# Power_Main_Regulators.net
KiCad netlist of a schematic drawn in Altium Designer
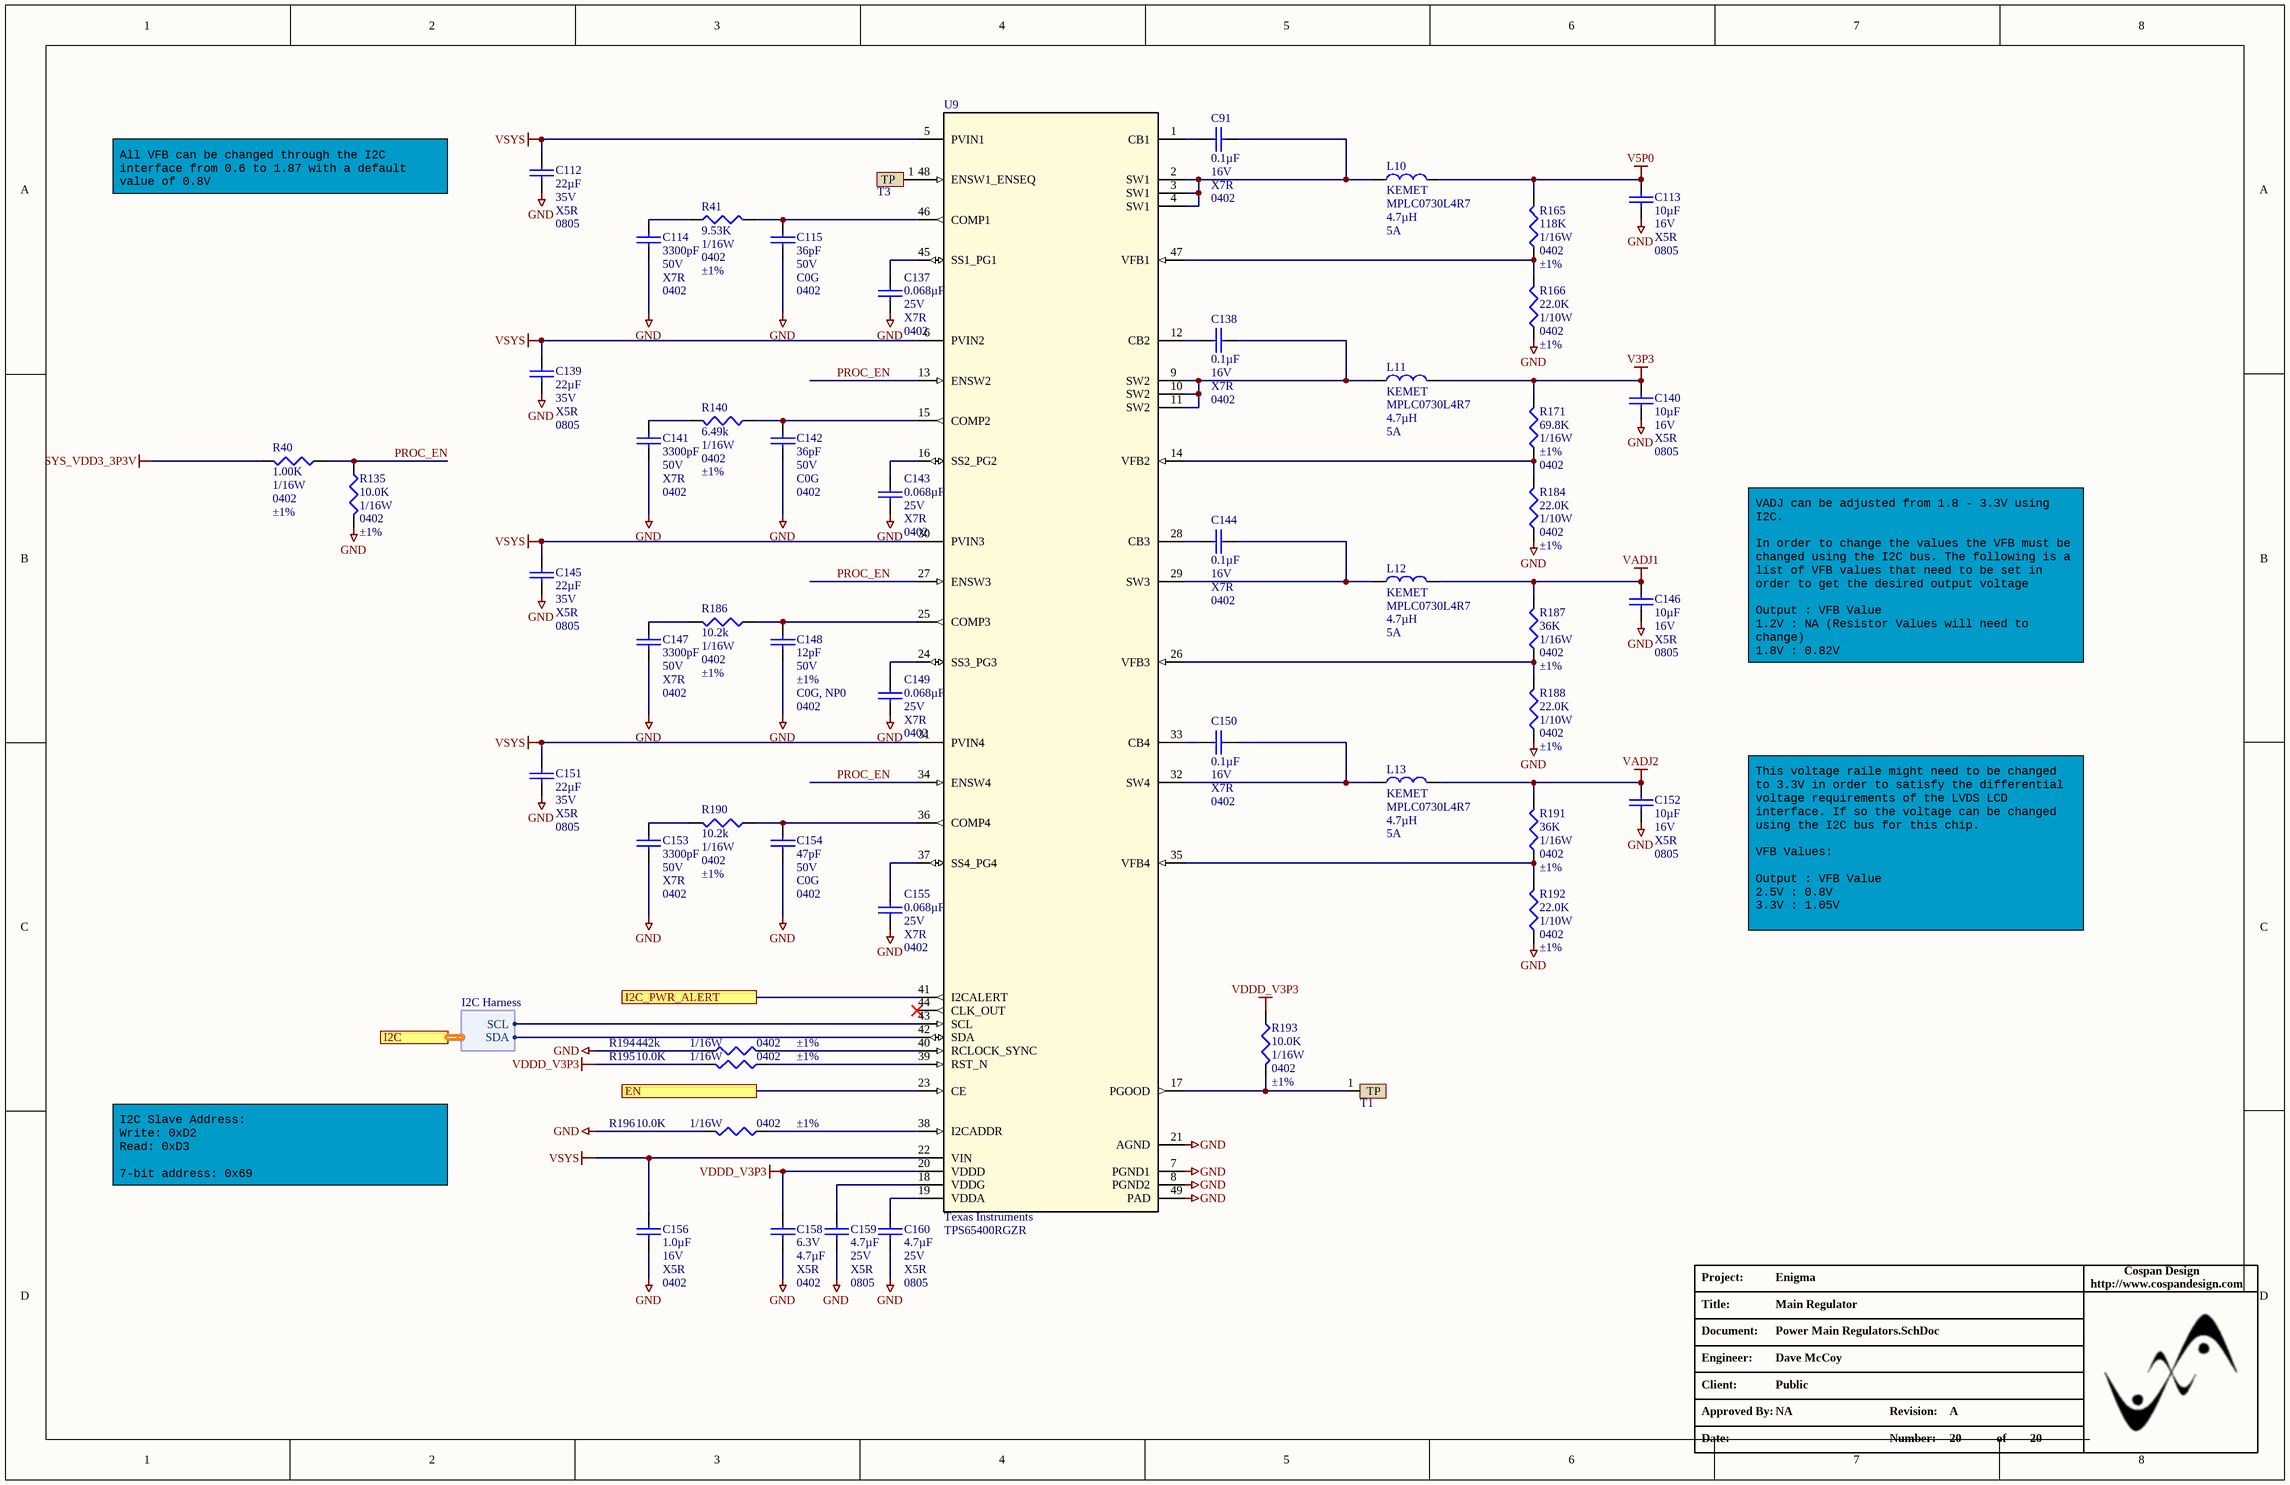
[diagram p0: Power Main Regulators.SchDoc]

(export (version "E")
  (design (tool "Eeschema 10.0.6"))
  (components
    (comp (ref "C91")
      (value "0.1uF")
      (footprint "C_0402")
      (description "CAP CER .10UF 16V X7R 0402")
      (fields
        (field (name "MANUFACTURER") "Murata Electronics North America")
        (field (name "MANUFACTURER PART NUMBER") "GRM155R71C104KA88J")
        (field (name "CAPACITANCE") "0.1µF")
        (field (name "VOLTAGE - RATED") "16V")
        (field (name "TEMPERATURE COEFFICIENT") "X7R")
        (field (name "PACKAGE / CASE") "0402")
      )
      (libsource (lib "Main LibraryX") (part "C_0402_0.1UF_16V"))
    )
    (comp (ref "C112")
      (value "C_0805_22µF_35V")
      (footprint "C_ERA-0805")
      (description "CAP CER 22UF 35V X5R 0805")
      (fields
        (field (name "MANUFACTURER") "TDK Corporation")
        (field (name "MANUFACTURER PART NUMBER") "C2012X5R1V226M125AC")
        (field (name "CAPACITANCE") "22µF")
        (field (name "VOLTAGE - RATED") "35V")
        (field (name "TEMPERATURE COEFFICIENT") "X5R")
        (field (name "PACKAGE / CASE") "0805")
      )
      (libsource (lib "Cospan Design") (part "C_0805_22µF_35V"))
    )
    (comp (ref "C113")
      (value "10µF")
      (footprint "C_ERA-0805")
      (description "CAP CER 10uF 16V X5R 20% 0805")
      (fields
        (field (name "MANUFACTURER") "Taiyo Yuden")
        (field (name "MANUFACTURER PART NUMBER") "EMK212BJ106KG-T")
        (field (name "CAPACITANCE") "10µF")
        (field (name "VOLTAGE - RATED") "16V")
        (field (name "TEMPERATURE COEFFICIENT") "X5R")
        (field (name "PACKAGE / CASE") "0805")
      )
      (libsource (lib "Main LibraryX") (part "C_0805_10UF_16V"))
    )
    (comp (ref "C114")
      (value "C_0402_3.3nF_50V")
      (footprint "C_0402")
      (fields
        (field (name "MANUFACTURER") "Murata Electronics North America")
        (field (name "MANUFACTURER PART NUMBER") "GRM155R71H332KA01D")
        (field (name "TOLERANCE") "±10%")
        (field (name "CAPACITANCE") "3300pF")
        (field (name "VOLTAGE - RATED") "50V")
        (field (name "TEMPERATURE COEFFICIENT") "X7R")
        (field (name "PACKAGE / CASE") "0402")
      )
      (libsource (lib "Main LibraryX") (part "C_0402_3.3nF_50V"))
    )
    (comp (ref "C115")
      (value "C_0402_36pF")
      (footprint "C_0402")
      (description "CAP CER 36PF 50V NP0 0402")
      (fields
        (field (name "MANUFACTURER") "Samsung Electro-Mechanics America, Inc.")
        (field (name "MANUFACTURER PART NUMBER") "CL05C360JB5NNNC")
        (field (name "CAPACITANCE") "36pF")
        (field (name "VOLTAGE - RATED") "50V")
        (field (name "TEMPERATURE COEFFICIENT") "C0G")
        (field (name "PACKAGE / CASE") "0402")
      )
      (libsource (lib "Cospan Design") (part "C_0402_36pF"))
    )
    (comp (ref "C137")
      (value "C_0402_68nF")
      (footprint "C_0402")
      (description "CAP CER 0.068UF 25V X7R 0402")
      (fields
        (field (name "MANUFACTURER") "Murata Electronics North America")
        (field (name "MANUFACTURER PART NUMBER") "GRM155R71E683KE14D")
        (field (name "CAPACITANCE") "0.068µF")
        (field (name "VOLTAGE - RATED") "25V")
        (field (name "TEMPERATURE COEFFICIENT") "X7R")
        (field (name "PACKAGE / CASE") "0402")
      )
      (libsource (lib "Cospan Design") (part "C_0402_68nF"))
    )
    (comp (ref "C138")
      (value "0.1uF")
      (footprint "C_0402")
      (description "CAP CER .10UF 16V X7R 0402")
      (fields
        (field (name "MANUFACTURER") "Murata Electronics North America")
        (field (name "MANUFACTURER PART NUMBER") "GRM155R71C104KA88J")
        (field (name "CAPACITANCE") "0.1µF")
        (field (name "VOLTAGE - RATED") "16V")
        (field (name "TEMPERATURE COEFFICIENT") "X7R")
        (field (name "PACKAGE / CASE") "0402")
      )
      (libsource (lib "Main LibraryX") (part "C_0402_0.1UF_16V"))
    )
    (comp (ref "C139")
      (value "C_0805_22µF_35V")
      (footprint "C_ERA-0805")
      (description "CAP CER 22UF 35V X5R 0805")
      (fields
        (field (name "MANUFACTURER") "TDK Corporation")
        (field (name "MANUFACTURER PART NUMBER") "C2012X5R1V226M125AC")
        (field (name "CAPACITANCE") "22µF")
        (field (name "VOLTAGE - RATED") "35V")
        (field (name "TEMPERATURE COEFFICIENT") "X5R")
        (field (name "PACKAGE / CASE") "0805")
      )
      (libsource (lib "Cospan Design") (part "C_0805_22µF_35V"))
    )
    (comp (ref "C140")
      (value "10µF")
      (footprint "C_ERA-0805")
      (description "CAP CER 10uF 16V X5R 20% 0805")
      (fields
        (field (name "MANUFACTURER") "Taiyo Yuden")
        (field (name "MANUFACTURER PART NUMBER") "EMK212BJ106KG-T")
        (field (name "CAPACITANCE") "10µF")
        (field (name "VOLTAGE - RATED") "16V")
        (field (name "TEMPERATURE COEFFICIENT") "X5R")
        (field (name "PACKAGE / CASE") "0805")
      )
      (libsource (lib "Main LibraryX") (part "C_0805_10UF_16V"))
    )
    (comp (ref "C141")
      (value "C_0402_3.3nF_50V")
      (footprint "C_0402")
      (fields
        (field (name "MANUFACTURER") "Murata Electronics North America")
        (field (name "MANUFACTURER PART NUMBER") "GRM155R71H332KA01D")
        (field (name "TOLERANCE") "±10%")
        (field (name "CAPACITANCE") "3300pF")
        (field (name "VOLTAGE - RATED") "50V")
        (field (name "TEMPERATURE COEFFICIENT") "X7R")
        (field (name "PACKAGE / CASE") "0402")
      )
      (libsource (lib "Main LibraryX") (part "C_0402_3.3nF_50V"))
    )
    (comp (ref "C142")
      (value "C_0402_36pF")
      (footprint "C_0402")
      (description "CAP CER 36PF 50V NP0 0402")
      (fields
        (field (name "MANUFACTURER") "Samsung Electro-Mechanics America, Inc.")
        (field (name "MANUFACTURER PART NUMBER") "CL05C360JB5NNNC")
        (field (name "CAPACITANCE") "36pF")
        (field (name "VOLTAGE - RATED") "50V")
        (field (name "TEMPERATURE COEFFICIENT") "C0G")
        (field (name "PACKAGE / CASE") "0402")
      )
      (libsource (lib "Cospan Design") (part "C_0402_36pF"))
    )
    (comp (ref "C143")
      (value "C_0402_68nF")
      (footprint "C_0402")
      (description "CAP CER 0.068UF 25V X7R 0402")
      (fields
        (field (name "MANUFACTURER") "Murata Electronics North America")
        (field (name "MANUFACTURER PART NUMBER") "GRM155R71E683KE14D")
        (field (name "CAPACITANCE") "0.068µF")
        (field (name "VOLTAGE - RATED") "25V")
        (field (name "TEMPERATURE COEFFICIENT") "X7R")
        (field (name "PACKAGE / CASE") "0402")
      )
      (libsource (lib "Cospan Design") (part "C_0402_68nF"))
    )
    (comp (ref "C144")
      (value "0.1uF")
      (footprint "C_0402")
      (description "CAP CER .10UF 16V X7R 0402")
      (fields
        (field (name "MANUFACTURER") "Murata Electronics North America")
        (field (name "MANUFACTURER PART NUMBER") "GRM155R71C104KA88J")
        (field (name "CAPACITANCE") "0.1µF")
        (field (name "VOLTAGE - RATED") "16V")
        (field (name "TEMPERATURE COEFFICIENT") "X7R")
        (field (name "PACKAGE / CASE") "0402")
      )
      (libsource (lib "Main LibraryX") (part "C_0402_0.1UF_16V"))
    )
    (comp (ref "C145")
      (value "C_0805_22µF_35V")
      (footprint "C_ERA-0805")
      (description "CAP CER 22UF 35V X5R 0805")
      (fields
        (field (name "MANUFACTURER") "TDK Corporation")
        (field (name "MANUFACTURER PART NUMBER") "C2012X5R1V226M125AC")
        (field (name "CAPACITANCE") "22µF")
        (field (name "VOLTAGE - RATED") "35V")
        (field (name "TEMPERATURE COEFFICIENT") "X5R")
        (field (name "PACKAGE / CASE") "0805")
      )
      (libsource (lib "Cospan Design") (part "C_0805_22µF_35V"))
    )
    (comp (ref "C146")
      (value "10µF")
      (footprint "C_ERA-0805")
      (description "CAP CER 10uF 16V X5R 20% 0805")
      (fields
        (field (name "MANUFACTURER") "Taiyo Yuden")
        (field (name "MANUFACTURER PART NUMBER") "EMK212BJ106KG-T")
        (field (name "CAPACITANCE") "10µF")
        (field (name "VOLTAGE - RATED") "16V")
        (field (name "TEMPERATURE COEFFICIENT") "X5R")
        (field (name "PACKAGE / CASE") "0805")
      )
      (libsource (lib "Main LibraryX") (part "C_0805_10UF_16V"))
    )
    (comp (ref "C147")
      (value "C_0402_3.3nF_50V")
      (footprint "C_0402")
      (fields
        (field (name "MANUFACTURER") "Murata Electronics North America")
        (field (name "MANUFACTURER PART NUMBER") "GRM155R71H332KA01D")
        (field (name "TOLERANCE") "±10%")
        (field (name "CAPACITANCE") "3300pF")
        (field (name "VOLTAGE - RATED") "50V")
        (field (name "TEMPERATURE COEFFICIENT") "X7R")
        (field (name "PACKAGE / CASE") "0402")
      )
      (libsource (lib "Main LibraryX") (part "C_0402_3.3nF_50V"))
    )
    (comp (ref "C148")
      (value "12pF")
      (footprint "C_0402")
      (description "CAP CER 12PF 50V 5% C0G 0402")
      (fields
        (field (name "MANUFACTURER") "Murata Electronics North America")
        (field (name "MANUFACTURER PART NUMBER") "GRM1555C1H120FA01D")
        (field (name "CAPACITANCE") "12pF")
        (field (name "VOLTAGE - RATED") "50V")
        (field (name "TOLERANCE") "±1%")
        (field (name "TEMPERATURE COEFFICIENT") "C0G, NP0")
        (field (name "PACKAGE / CASE") "0402")
      )
      (libsource (lib "Main LibraryX") (part "C_0402_12PF_50V"))
    )
    (comp (ref "C149")
      (value "C_0402_68nF")
      (footprint "C_0402")
      (description "CAP CER 0.068UF 25V X7R 0402")
      (fields
        (field (name "MANUFACTURER") "Murata Electronics North America")
        (field (name "MANUFACTURER PART NUMBER") "GRM155R71E683KE14D")
        (field (name "CAPACITANCE") "0.068µF")
        (field (name "VOLTAGE - RATED") "25V")
        (field (name "TEMPERATURE COEFFICIENT") "X7R")
        (field (name "PACKAGE / CASE") "0402")
      )
      (libsource (lib "Cospan Design") (part "C_0402_68nF"))
    )
    (comp (ref "C150")
      (value "0.1uF")
      (footprint "C_0402")
      (description "CAP CER .10UF 16V X7R 0402")
      (fields
        (field (name "MANUFACTURER") "Murata Electronics North America")
        (field (name "MANUFACTURER PART NUMBER") "GRM155R71C104KA88J")
        (field (name "CAPACITANCE") "0.1µF")
        (field (name "VOLTAGE - RATED") "16V")
        (field (name "TEMPERATURE COEFFICIENT") "X7R")
        (field (name "PACKAGE / CASE") "0402")
      )
      (libsource (lib "Main LibraryX") (part "C_0402_0.1UF_16V"))
    )
    (comp (ref "C151")
      (value "C_0805_22µF_35V")
      (footprint "C_ERA-0805")
      (description "CAP CER 22UF 35V X5R 0805")
      (fields
        (field (name "MANUFACTURER") "TDK Corporation")
        (field (name "MANUFACTURER PART NUMBER") "C2012X5R1V226M125AC")
        (field (name "CAPACITANCE") "22µF")
        (field (name "VOLTAGE - RATED") "35V")
        (field (name "TEMPERATURE COEFFICIENT") "X5R")
        (field (name "PACKAGE / CASE") "0805")
      )
      (libsource (lib "Cospan Design") (part "C_0805_22µF_35V"))
    )
    (comp (ref "C152")
      (value "10µF")
      (footprint "C_ERA-0805")
      (description "CAP CER 10uF 16V X5R 20% 0805")
      (fields
        (field (name "MANUFACTURER") "Taiyo Yuden")
        (field (name "MANUFACTURER PART NUMBER") "EMK212BJ106KG-T")
        (field (name "CAPACITANCE") "10µF")
        (field (name "VOLTAGE - RATED") "16V")
        (field (name "TEMPERATURE COEFFICIENT") "X5R")
        (field (name "PACKAGE / CASE") "0805")
      )
      (libsource (lib "Main LibraryX") (part "C_0805_10UF_16V"))
    )
    (comp (ref "C153")
      (value "C_0402_3.3nF_50V")
      (footprint "C_0402")
      (fields
        (field (name "MANUFACTURER") "Murata Electronics North America")
        (field (name "MANUFACTURER PART NUMBER") "GRM155R71H332KA01D")
        (field (name "TOLERANCE") "±10%")
        (field (name "CAPACITANCE") "3300pF")
        (field (name "VOLTAGE - RATED") "50V")
        (field (name "TEMPERATURE COEFFICIENT") "X7R")
        (field (name "PACKAGE / CASE") "0402")
      )
      (libsource (lib "Main LibraryX") (part "C_0402_3.3nF_50V"))
    )
    (comp (ref "C154")
      (value "47pF")
      (footprint "C_0402")
      (description "CAP CER 47PF 50V 5% C0G 0402")
      (fields
        (field (name "MANUFACTURER") "Murata Electronics North America")
        (field (name "MANUFACTURER PART NUMBER") "GRM1555C1H470JA01D")
        (field (name "CAPACITANCE") "47pF")
        (field (name "VOLTAGE - RATED") "50V")
        (field (name "TEMPERATURE COEFFICIENT") "C0G")
        (field (name "PACKAGE / CASE") "0402")
      )
      (libsource (lib "Main Library") (part "C_0402_47p_50V"))
    )
    (comp (ref "C155")
      (value "C_0402_68nF")
      (footprint "C_0402")
      (description "CAP CER 0.068UF 25V X7R 0402")
      (fields
        (field (name "MANUFACTURER") "Murata Electronics North America")
        (field (name "MANUFACTURER PART NUMBER") "GRM155R71E683KE14D")
        (field (name "CAPACITANCE") "0.068µF")
        (field (name "VOLTAGE - RATED") "25V")
        (field (name "TEMPERATURE COEFFICIENT") "X7R")
        (field (name "PACKAGE / CASE") "0402")
      )
      (libsource (lib "Cospan Design") (part "C_0402_68nF"))
    )
    (comp (ref "C156")
      (value "1.0uF")
      (footprint "C_0402")
      (description "CAP CER 1.0UF 16V X5R 0402")
      (fields
        (field (name "TOLERANCE") "10%")
        (field (name "VOLTAGE") "16V")
        (field (name "CAPACITANCE") "1.0µF")
        (field (name "VOLTAGE - RATED") "16V")
        (field (name "TEMPERATURE COEFFICIENT") "X5R")
        (field (name "PACKAGE / CASE") "0402")
      )
      (libsource (lib "Main Library") (part "C_0402_1.0UF_16V"))
    )
    (comp (ref "C158")
      (value "4.7uF")
      (footprint "C_0402")
      (description "CAP CER 4.7UF 6.3V X5R 0402")
      (fields
        (field (name "MANUFACTURER") "Samsung Electro-Mechanics America, Inc")
        (field (name "MANUFACTURER PART NUMBER") "CL05A475MQ5NRNC")
        (field (name "VOLTAGE - RATED") "6.3V")
        (field (name "CAPACITANCE") "4.7µF")
        (field (name "TEMPERATURE COEFFICIENT") "X5R")
        (field (name "PACKAGE / CASE") "0402")
      )
      (libsource (lib "Main Library") (part "C_0402_4.7UF"))
    )
    (comp (ref "C159")
      (value "4.7µF")
      (footprint "C_ERA-0805")
      (description "CAP CER 4.7UF 25V 10% X5R 0805")
      (fields
        (field (name "MANUFACTURER") "Taiyo Yuden")
        (field (name "MANUFACTURER PART NUMBER") "TMK212BJ475KG-T")
        (field (name "CAPACITANCE") "4.7µF")
        (field (name "VOLTAGE - RATED") "25V")
        (field (name "TEMPERATURE COEFFICIENT") "X5R")
        (field (name "PACKAGE / CASE") "0805")
      )
      (libsource (lib "Main Library") (part "C_0805_4.7µF_25V"))
    )
    (comp (ref "C160")
      (value "4.7µF")
      (footprint "C_ERA-0805")
      (description "CAP CER 4.7UF 25V 10% X5R 0805")
      (fields
        (field (name "MANUFACTURER") "Taiyo Yuden")
        (field (name "MANUFACTURER PART NUMBER") "TMK212BJ475KG-T")
        (field (name "CAPACITANCE") "4.7µF")
        (field (name "VOLTAGE - RATED") "25V")
        (field (name "TEMPERATURE COEFFICIENT") "X5R")
        (field (name "PACKAGE / CASE") "0805")
      )
      (libsource (lib "Main Library") (part "C_0805_4.7µF_25V"))
    )
    (comp (ref "L10")
      (value "L_MPLC0730L4R7")
      (footprint "KEM_L9004_MPLC")
      (description "FIXED IND 4.7UH 5A 41 MOHM SMD")
      (fields
        (field (name "TOLERANCE") "±20%")
        (field (name "MANUFACTURER") "KEMET")
        (field (name "MANUFACTURER PART NUMBER") "MPLC0730L4R7")
        (field (name "INDUCTANCE") "4.7µH")
        (field (name "MAX DC CURRENT") "5A")
      )
      (libsource (lib "Cospan Design") (part "L_MPLC0730L4R7"))
    )
    (comp (ref "L11")
      (value "L_MPLC0730L4R7")
      (footprint "KEM_L9004_MPLC")
      (description "FIXED IND 4.7UH 5A 41 MOHM SMD")
      (fields
        (field (name "TOLERANCE") "±20%")
        (field (name "MANUFACTURER") "KEMET")
        (field (name "MANUFACTURER PART NUMBER") "MPLC0730L4R7")
        (field (name "INDUCTANCE") "4.7µH")
        (field (name "MAX DC CURRENT") "5A")
      )
      (libsource (lib "Cospan Design") (part "L_MPLC0730L4R7"))
    )
    (comp (ref "L12")
      (value "L_MPLC0730L4R7")
      (footprint "KEM_L9004_MPLC")
      (description "FIXED IND 4.7UH 5A 41 MOHM SMD")
      (fields
        (field (name "TOLERANCE") "±20%")
        (field (name "MANUFACTURER") "KEMET")
        (field (name "MANUFACTURER PART NUMBER") "MPLC0730L4R7")
        (field (name "INDUCTANCE") "4.7µH")
        (field (name "MAX DC CURRENT") "5A")
      )
      (libsource (lib "Cospan Design") (part "L_MPLC0730L4R7"))
    )
    (comp (ref "L13")
      (value "L_MPLC0730L4R7")
      (footprint "KEM_L9004_MPLC")
      (description "FIXED IND 4.7UH 5A 41 MOHM SMD")
      (fields
        (field (name "TOLERANCE") "±20%")
        (field (name "MANUFACTURER") "KEMET")
        (field (name "MANUFACTURER PART NUMBER") "MPLC0730L4R7")
        (field (name "INDUCTANCE") "4.7µH")
        (field (name "MAX DC CURRENT") "5A")
      )
      (libsource (lib "Cospan Design") (part "L_MPLC0730L4R7"))
    )
    (comp (ref "R40")
      (value "1.0k Ohms")
      (footprint "R_0402")
      (description "RES 1.00K OHM 1/16W 1% 0402 SMD")
      (fields
        (field (name "MANUFACTURER") "Yageo")
        (field (name "MANUFACTURER PART NUMBER") "RC0402FR-071KL")
        (field (name "RESISTANCE IN OHMS") "1.00K")
        (field (name "POWER (WATTS)") "1/16W")
        (field (name "CASE") "0402")
        (field (name "TOLERANCE") "±1%")
      )
      (libsource (lib "Main Library") (part "R_0402_1.0K"))
    )
    (comp (ref "R41")
      (value "R_0402_9.53K")
      (footprint "R_0402")
      (description "RES SMD 9.53K OHM 1% 1/16W 0402")
      (fields
        (field (name "MANUFACTURER") "Yageo")
        (field (name "MANUFACTURER PART NUMBER") "RC0402FR-079K53L")
        (field (name "RESISTANCE IN OHMS") "9.53K")
        (field (name "POWER (WATTS)") "1/16W")
        (field (name "CASE") "0402")
        (field (name "TOLERANCE") "±1%")
      )
      (libsource (lib "Cospan Design") (part "R_0402_9.53K"))
    )
    (comp (ref "R135")
      (value "R_0402_10.0K")
      (footprint "R_0402")
      (description "RES 10.0K OHM 1/16W 1% 0402 SMD")
      (fields
        (field (name "MANUFACTURER") "Stackpole Electronics Inc")
        (field (name "MANUFACTURER PART NUMBER") "RMCF0402FT10K0")
        (field (name "RESISTANCE IN OHMS") "10.0K")
        (field (name "POWER (WATTS)") "1/16W")
        (field (name "CASE") "0402")
        (field (name "TOLERANCE") "±1%")
      )
      (libsource (lib "Cospan Design") (part "R_0402_10.0K"))
    )
    (comp (ref "R140")
      (value "R_0402_6.49k")
      (footprint "R_0402")
      (description "RES SMD 6.49K OHM 1% 1/16W 0402")
      (fields
        (field (name "MANUFACTURER") "Samsung Electro-Mechanics America, Inc.")
        (field (name "MANUFACTURER PART NUMBER") "RC1005F6491CS")
        (field (name "RESISTANCE IN OHMS") "6.49k")
        (field (name "POWER (WATTS)") "1/16W")
        (field (name "CASE") "0402")
        (field (name "TOLERANCE") "±1%")
      )
      (libsource (lib "Cospan Design") (part "R_0402_6.49k"))
    )
    (comp (ref "R165")
      (value "R_0402_118K")
      (footprint "R_0402")
      (description "RES SMD 118K OHM 1% 1/16W 0402")
      (fields
        (field (name "MANUFACTURER") "Stackpole Electronics Inc")
        (field (name "MANUFACTURER PART NUMBER") "RMCF0402FT118K")
        (field (name "RESISTANCE IN OHMS") "118K")
        (field (name "POWER (WATTS)") "1/16W")
        (field (name "CASE") "0402")
        (field (name "TOLERANCE") "±1%")
      )
      (libsource (lib "Cospan Design") (part "R_0402_118K"))
    )
    (comp (ref "R166")
      (value "R_0402_22.0K")
      (footprint "R_0402")
      (description "RES 22.0K OHM 1/10W 1% 0402 SMD")
      (fields
        (field (name "MANUFACTURER") "Vishay Dale")
        (field (name "MANUFACTURER PART NUMBER") "CRCW040222K0FKED")
        (field (name "RESISTANCE IN OHMS") "22.0K")
        (field (name "POWER (WATTS)") "1/10W")
        (field (name "CASE") "0402")
        (field (name "TOLERANCE") "±1%")
      )
      (libsource (lib "Main Library") (part "R_0402_22.0K"))
    )
    (comp (ref "R171")
      (value "R_0402_69.8K")
      (footprint "R_0402")
      (description "RES 69.8K OHM 1/16W 1% 0402 SMD")
      (fields
        (field (name "MANUFACTURER") "Yageo")
        (field (name "MANUFACTURER PART NUMBER") "RC0402FR-0769K8L")
        (field (name "RESISTANCE IN OHMS") "69.8K")
        (field (name "POWER (WATTS)") "1/16W")
        (field (name "TOLERANCE") "±1%")
        (field (name "CASE") "0402")
      )
      (libsource (lib "Main LibraryX") (part "R_0402_69.8K"))
    )
    (comp (ref "R184")
      (value "R_0402_22.0K")
      (footprint "R_0402")
      (description "RES 22.0K OHM 1/10W 1% 0402 SMD")
      (fields
        (field (name "MANUFACTURER") "Vishay Dale")
        (field (name "MANUFACTURER PART NUMBER") "CRCW040222K0FKED")
        (field (name "RESISTANCE IN OHMS") "22.0K")
        (field (name "POWER (WATTS)") "1/10W")
        (field (name "CASE") "0402")
        (field (name "TOLERANCE") "±1%")
      )
      (libsource (lib "Main Library") (part "R_0402_22.0K"))
    )
    (comp (ref "R186")
      (value "R_0402_10.2k")
      (footprint "R_0402")
      (description "RES SMD 10.2K OHM 1% 1/16W 0402")
      (fields
        (field (name "MANUFACTURER") "Stackpole Electronics Inc.")
        (field (name "MANUFACTURER PART NUMBER") "RMCF0402FT10K2")
        (field (name "RESISTANCE IN OHMS") "10.2k")
        (field (name "POWER (WATTS)") "1/16W")
        (field (name "CASE") "0402")
        (field (name "TOLERANCE") "±1%")
      )
      (libsource (lib "Cospan Design") (part "R_0402_10.2k"))
    )
    (comp (ref "R187")
      (value "R_0402_36.0K")
      (footprint "R_0402")
      (description "RES 36.0K OHM 1/10W 1% 0402 SMD")
      (fields
        (field (name "MANUFACTURER") "Panasonic - ECG")
        (field (name "MANUFACTURER PART NUMBER") "ERJ-2RKF3602X")
        (field (name "RESISTANCE IN OHMS") "36K")
        (field (name "POWER (WATTS)") "1/16W")
        (field (name "CASE") "0402")
        (field (name "TOLERANCE") "±1%")
      )
      (libsource (lib "Main Library") (part "R_0402_36.0K"))
    )
    (comp (ref "R188")
      (value "R_0402_22.0K")
      (footprint "R_0402")
      (description "RES 22.0K OHM 1/10W 1% 0402 SMD")
      (fields
        (field (name "MANUFACTURER") "Vishay Dale")
        (field (name "MANUFACTURER PART NUMBER") "CRCW040222K0FKED")
        (field (name "RESISTANCE IN OHMS") "22.0K")
        (field (name "POWER (WATTS)") "1/10W")
        (field (name "CASE") "0402")
        (field (name "TOLERANCE") "±1%")
      )
      (libsource (lib "Main Library") (part "R_0402_22.0K"))
    )
    (comp (ref "R190")
      (value "R_0402_10.2k")
      (footprint "R_0402")
      (description "RES SMD 10.2K OHM 1% 1/16W 0402")
      (fields
        (field (name "MANUFACTURER") "Stackpole Electronics Inc.")
        (field (name "MANUFACTURER PART NUMBER") "RMCF0402FT10K2")
        (field (name "RESISTANCE IN OHMS") "10.2k")
        (field (name "POWER (WATTS)") "1/16W")
        (field (name "CASE") "0402")
        (field (name "TOLERANCE") "±1%")
      )
      (libsource (lib "Cospan Design") (part "R_0402_10.2k"))
    )
    (comp (ref "R191")
      (value "R_0402_36.0K")
      (footprint "R_0402")
      (description "RES 36.0K OHM 1/10W 1% 0402 SMD")
      (fields
        (field (name "MANUFACTURER") "Panasonic - ECG")
        (field (name "MANUFACTURER PART NUMBER") "ERJ-2RKF3602X")
        (field (name "RESISTANCE IN OHMS") "36K")
        (field (name "POWER (WATTS)") "1/16W")
        (field (name "CASE") "0402")
        (field (name "TOLERANCE") "±1%")
      )
      (libsource (lib "Main Library") (part "R_0402_36.0K"))
    )
    (comp (ref "R192")
      (value "R_0402_22.0K")
      (footprint "R_0402")
      (description "RES 22.0K OHM 1/10W 1% 0402 SMD")
      (fields
        (field (name "MANUFACTURER") "Vishay Dale")
        (field (name "MANUFACTURER PART NUMBER") "CRCW040222K0FKED")
        (field (name "RESISTANCE IN OHMS") "22.0K")
        (field (name "POWER (WATTS)") "1/10W")
        (field (name "CASE") "0402")
        (field (name "TOLERANCE") "±1%")
      )
      (libsource (lib "Main Library") (part "R_0402_22.0K"))
    )
    (comp (ref "R193")
      (value "R_0402_10.0K")
      (footprint "R_0402")
      (description "RES 10.0K OHM 1/16W 1% 0402 SMD")
      (fields
        (field (name "MANUFACTURER") "Stackpole Electronics Inc")
        (field (name "MANUFACTURER PART NUMBER") "RMCF0402FT10K0")
        (field (name "RESISTANCE IN OHMS") "10.0K")
        (field (name "POWER (WATTS)") "1/16W")
        (field (name "CASE") "0402")
        (field (name "TOLERANCE") "±1%")
      )
      (libsource (lib "Cospan Design") (part "R_0402_10.0K"))
    )
    (comp (ref "R194")
      (value "R_0402_442k")
      (footprint "R_0402")
      (description "RES SMD 442K OHM 1% 1/16W 0402")
      (fields
        (field (name "MANUFACTURER") "Yageo")
        (field (name "MANUFACTURER PART NUMBER") "RC0402FR-07442KL")
        (field (name "RESISTANCE IN OHMS") "442k")
        (field (name "POWER (WATTS)") "1/16W")
        (field (name "CASE") "0402")
        (field (name "TOLERANCE") "±1%")
      )
      (libsource (lib "Cospan Design") (part "R_0402_442k"))
    )
    (comp (ref "R195")
      (value "R_0402_10.0K")
      (footprint "R_0402")
      (description "RES 10.0K OHM 1/16W 1% 0402 SMD")
      (fields
        (field (name "MANUFACTURER") "Stackpole Electronics Inc")
        (field (name "MANUFACTURER PART NUMBER") "RMCF0402FT10K0")
        (field (name "RESISTANCE IN OHMS") "10.0K")
        (field (name "POWER (WATTS)") "1/16W")
        (field (name "CASE") "0402")
        (field (name "TOLERANCE") "±1%")
      )
      (libsource (lib "Cospan Design") (part "R_0402_10.0K"))
    )
    (comp (ref "R196")
      (value "R_0402_10.0K")
      (footprint "R_0402")
      (description "RES 10.0K OHM 1/16W 1% 0402 SMD")
      (fields
        (field (name "MANUFACTURER") "Stackpole Electronics Inc")
        (field (name "MANUFACTURER PART NUMBER") "RMCF0402FT10K0")
        (field (name "RESISTANCE IN OHMS") "10.0K")
        (field (name "POWER (WATTS)") "1/16W")
        (field (name "CASE") "0402")
        (field (name "TOLERANCE") "±1%")
      )
      (libsource (lib "Cospan Design") (part "R_0402_10.0K"))
    )
    (comp (ref "T1")
      (value "TEST_POINT_SMALL")
      (footprint "TestPointSmall")
      (description "OSCILLOSCOPE TEST POINT")
      (libsource (lib "") (part "TEST_POINT_SMALL_1"))
    )
    (comp (ref "T3")
      (value "TEST_POINT_SMALL")
      (footprint "TestPointSmall")
      (description "OSCILLOSCOPE TEST POINT")
      (libsource (lib "Main LibraryX") (part "TEST_POINT_SMALL"))
    )
    (comp (ref "U9")
      (value "U_TPS65400RGZR")
      (footprint "RGZ0048B")
      (description "IC REG BUCK ADJ 4A/2A QD 48VQFN")
      (fields
        (field (name "MANUFACTURER") "Texas Instruments")
        (field (name "MANUFACTURER PART NUMBER") "TPS65400RGZR")
      )
      (libsource (lib "Cospan Design") (part "U_TPS65400RGZR"))
    )
  )
  (nets
    (net (code "3") (name "/EN") (class "Default")
      (node (ref "U9") (pin "23") (pinfunction "CE_23") (pintype "input"))
    )
    (net (code "4") (name "/I2C_PWR_ALERT") (class "Default")
      (node (ref "U9") (pin "41") (pinfunction "I2CALERT_41") (pintype "output"))
    )
    (net (code "5") (name "/PROC_EN") (class "Default")
      (node (ref "R135") (pin "2") (pinfunction "2_2") (pintype "passive"))
      (node (ref "R40") (pin "2") (pinfunction "2_2") (pintype "passive"))
      (node (ref "U9") (pin "13") (pinfunction "ENSW2_13") (pintype "input"))
      (node (ref "U9") (pin "27") (pinfunction "ENSW3_27") (pintype "input"))
      (node (ref "U9") (pin "34") (pinfunction "ENSW4_34") (pintype "input"))
    )
    (net (code "6") (name "/SCL") (class "Default")
      (node (ref "U9") (pin "43") (pinfunction "SCL_43") (pintype "input"))
    )
    (net (code "7") (name "/SDA") (class "Default")
      (node (ref "U9") (pin "42") (pinfunction "SDA_42") (pintype "bidirectional"))
    )
    (net (code "9") (name "GND") (class "Default")
      (node (ref "C112") (pin "1") (pinfunction "1_1") (pintype "passive"))
      (node (ref "C113") (pin "1") (pinfunction "1_1") (pintype "passive"))
      (node (ref "C114") (pin "1") (pinfunction "1_1") (pintype "passive"))
      (node (ref "C115") (pin "1") (pinfunction "1_1") (pintype "passive"))
      (node (ref "C137") (pin "1") (pinfunction "1_1") (pintype "passive"))
      (node (ref "C139") (pin "1") (pinfunction "1_1") (pintype "passive"))
      (node (ref "C140") (pin "1") (pinfunction "1_1") (pintype "passive"))
      (node (ref "C141") (pin "1") (pinfunction "1_1") (pintype "passive"))
      (node (ref "C142") (pin "1") (pinfunction "1_1") (pintype "passive"))
      (node (ref "C143") (pin "1") (pinfunction "1_1") (pintype "passive"))
      (node (ref "C145") (pin "1") (pinfunction "1_1") (pintype "passive"))
      (node (ref "C146") (pin "1") (pinfunction "1_1") (pintype "passive"))
      (node (ref "C147") (pin "1") (pinfunction "1_1") (pintype "passive"))
      (node (ref "C148") (pin "1") (pinfunction "1_1") (pintype "passive"))
      (node (ref "C149") (pin "1") (pinfunction "1_1") (pintype "passive"))
      (node (ref "C151") (pin "1") (pinfunction "1_1") (pintype "passive"))
      (node (ref "C152") (pin "1") (pinfunction "1_1") (pintype "passive"))
      (node (ref "C153") (pin "1") (pinfunction "1_1") (pintype "passive"))
      (node (ref "C154") (pin "1") (pinfunction "1_1") (pintype "passive"))
      (node (ref "C155") (pin "1") (pinfunction "1_1") (pintype "passive"))
      (node (ref "C156") (pin "1") (pinfunction "1_1") (pintype "passive"))
      (node (ref "C158") (pin "1") (pinfunction "1_1") (pintype "passive"))
      (node (ref "C159") (pin "1") (pinfunction "1_1") (pintype "passive"))
      (node (ref "C160") (pin "1") (pinfunction "1_1") (pintype "passive"))
      (node (ref "R135") (pin "1") (pinfunction "1_1") (pintype "passive"))
      (node (ref "R166") (pin "2") (pinfunction "2_2") (pintype "passive"))
      (node (ref "R184") (pin "2") (pinfunction "2_2") (pintype "passive"))
      (node (ref "R188") (pin "2") (pinfunction "2_2") (pintype "passive"))
      (node (ref "R192") (pin "2") (pinfunction "2_2") (pintype "passive"))
      (node (ref "R194") (pin "2") (pinfunction "2_2") (pintype "passive"))
      (node (ref "R196") (pin "1") (pinfunction "1_1") (pintype "passive"))
      (node (ref "U9") (pin "21") (pinfunction "AGND_21") (pintype "power_in"))
      (node (ref "U9") (pin "49") (pinfunction "PAD_49") (pintype "passive"))
      (node (ref "U9") (pin "7") (pinfunction "PGND1_7") (pintype "power_in"))
      (node (ref "U9") (pin "8") (pinfunction "PGND2_8") (pintype "power_in"))
    )
    (net (code "10") (name "Net-(C91-Pad1)") (class "Default")
      (node (ref "C91") (pin "1") (pinfunction "1_1") (pintype "passive"))
      (node (ref "L10") (pin "2") (pintype "passive"))
      (node (ref "U9") (pin "2") (pinfunction "SW1_2") (pintype "power_in"))
      (node (ref "U9") (pin "3") (pinfunction "SW1_3") (pintype "power_in"))
      (node (ref "U9") (pin "4") (pinfunction "SW1_4") (pintype "power_in"))
    )
    (net (code "11") (name "Net-(C114-Pad2)") (class "Default")
      (node (ref "C114") (pin "2") (pinfunction "2_2") (pintype "passive"))
      (node (ref "R41") (pin "2") (pinfunction "2_2") (pintype "passive"))
    )
    (net (code "12") (name "Net-(C138-Pad1)") (class "Default")
      (node (ref "C138") (pin "1") (pinfunction "1_1") (pintype "passive"))
      (node (ref "L11") (pin "2") (pintype "passive"))
      (node (ref "U9") (pin "10") (pinfunction "SW2_10") (pintype "passive"))
      (node (ref "U9") (pin "11") (pinfunction "SW2_11") (pintype "power_in"))
      (node (ref "U9") (pin "9") (pinfunction "SW2_9") (pintype "power_in"))
    )
    (net (code "13") (name "Net-(C141-Pad2)") (class "Default")
      (node (ref "C141") (pin "2") (pinfunction "2_2") (pintype "passive"))
      (node (ref "R140") (pin "1") (pinfunction "1_1") (pintype "passive"))
    )
    (net (code "14") (name "Net-(C147-Pad2)") (class "Default")
      (node (ref "C147") (pin "2") (pinfunction "2_2") (pintype "passive"))
      (node (ref "R186") (pin "1") (pinfunction "1_1") (pintype "passive"))
    )
    (net (code "15") (name "Net-(C153-Pad2)") (class "Default")
      (node (ref "C153") (pin "2") (pinfunction "2_2") (pintype "passive"))
      (node (ref "R190") (pin "1") (pinfunction "1_1") (pintype "passive"))
    )
    (net (code "16") (name "Net-(T1-TP)") (class "Default")
      (node (ref "R193") (pin "1") (pinfunction "1_1") (pintype "passive"))
      (node (ref "T1") (pin "1") (pinfunction "TP_1") (pintype "passive"))
      (node (ref "U9") (pin "17") (pinfunction "PGOOD_17") (pintype "output"))
    )
    (net (code "17") (name "Net-(T3-TP)") (class "Default")
      (node (ref "T3") (pin "1") (pinfunction "TP_1") (pintype "passive"))
      (node (ref "U9") (pin "48") (pinfunction "ENSW1_ENSEQ_48") (pintype "input"))
    )
    (net (code "18") (name "Net-(U9-CB1)") (class "Default")
      (node (ref "C91") (pin "2") (pinfunction "2_2") (pintype "passive"))
      (node (ref "U9") (pin "1") (pinfunction "CB1_1") (pintype "power_in"))
    )
    (net (code "19") (name "Net-(U9-CB2)") (class "Default")
      (node (ref "C138") (pin "2") (pinfunction "2_2") (pintype "passive"))
      (node (ref "U9") (pin "12") (pinfunction "CB2_12") (pintype "power_in"))
    )
    (net (code "20") (name "Net-(U9-CB3)") (class "Default")
      (node (ref "C144") (pin "2") (pinfunction "2_2") (pintype "passive"))
      (node (ref "U9") (pin "28") (pinfunction "CB3_28") (pintype "power_in"))
    )
    (net (code "21") (name "Net-(U9-CB4)") (class "Default")
      (node (ref "C150") (pin "2") (pinfunction "2_2") (pintype "passive"))
      (node (ref "U9") (pin "33") (pinfunction "CB4_33") (pintype "power_in"))
    )
    (net (code "22") (name "Net-(U9-COMP1)") (class "Default")
      (node (ref "C115") (pin "2") (pinfunction "2_2") (pintype "passive"))
      (node (ref "R41") (pin "1") (pinfunction "1_1") (pintype "passive"))
      (node (ref "U9") (pin "46") (pinfunction "COMP1_46") (pintype "output"))
    )
    (net (code "23") (name "Net-(U9-COMP2)") (class "Default")
      (node (ref "C142") (pin "2") (pinfunction "2_2") (pintype "passive"))
      (node (ref "R140") (pin "2") (pinfunction "2_2") (pintype "passive"))
      (node (ref "U9") (pin "15") (pinfunction "COMP2_15") (pintype "output"))
    )
    (net (code "24") (name "Net-(U9-COMP3)") (class "Default")
      (node (ref "C148") (pin "2") (pinfunction "2_2") (pintype "passive"))
      (node (ref "R186") (pin "2") (pinfunction "2_2") (pintype "passive"))
      (node (ref "U9") (pin "25") (pinfunction "COMP3_25") (pintype "output"))
    )
    (net (code "25") (name "Net-(U9-COMP4)") (class "Default")
      (node (ref "C154") (pin "2") (pinfunction "2_2") (pintype "passive"))
      (node (ref "R190") (pin "2") (pinfunction "2_2") (pintype "passive"))
      (node (ref "U9") (pin "36") (pinfunction "COMP4_36") (pintype "output"))
    )
    (net (code "26") (name "Net-(U9-I2CADDR)") (class "Default")
      (node (ref "R196") (pin "2") (pinfunction "2_2") (pintype "passive"))
      (node (ref "U9") (pin "38") (pinfunction "I2CADDR_38") (pintype "input"))
    )
    (net (code "27") (name "Net-(U9-RCLOCK_SYNC)") (class "Default")
      (node (ref "R194") (pin "1") (pinfunction "1_1") (pintype "passive"))
      (node (ref "U9") (pin "40") (pinfunction "RCLOCK_SYNC_40") (pintype "input"))
    )
    (net (code "28") (name "Net-(U9-RST_N)") (class "Default")
      (node (ref "R195") (pin "2") (pinfunction "2_2") (pintype "passive"))
      (node (ref "U9") (pin "39") (pinfunction "RST_N_39") (pintype "input"))
    )
    (net (code "29") (name "Net-(U9-SS1_PG1)") (class "Default")
      (node (ref "C137") (pin "2") (pinfunction "2_2") (pintype "passive"))
      (node (ref "U9") (pin "45") (pinfunction "SS1_PG1_45") (pintype "bidirectional"))
    )
    (net (code "30") (name "Net-(U9-SS2_PG2)") (class "Default")
      (node (ref "C143") (pin "2") (pinfunction "2_2") (pintype "passive"))
      (node (ref "U9") (pin "16") (pinfunction "SS2_PG2_16") (pintype "bidirectional"))
    )
    (net (code "31") (name "Net-(U9-SS3_PG3)") (class "Default")
      (node (ref "C149") (pin "2") (pinfunction "2_2") (pintype "passive"))
      (node (ref "U9") (pin "24") (pinfunction "SS3_PG3_24") (pintype "bidirectional"))
    )
    (net (code "32") (name "Net-(U9-SS4_PG4)") (class "Default")
      (node (ref "C155") (pin "2") (pinfunction "2_2") (pintype "passive"))
      (node (ref "U9") (pin "37") (pinfunction "SS4_PG4_37") (pintype "bidirectional"))
    )
    (net (code "33") (name "Net-(U9-SW3)") (class "Default")
      (node (ref "C144") (pin "1") (pinfunction "1_1") (pintype "passive"))
      (node (ref "L12") (pin "2") (pintype "passive"))
      (node (ref "U9") (pin "29") (pinfunction "SW3_29") (pintype "power_in"))
    )
    (net (code "34") (name "Net-(U9-SW4)") (class "Default")
      (node (ref "C150") (pin "1") (pinfunction "1_1") (pintype "passive"))
      (node (ref "L13") (pin "2") (pintype "passive"))
      (node (ref "U9") (pin "32") (pinfunction "SW4_32") (pintype "power_in"))
    )
    (net (code "35") (name "Net-(U9-VDDA)") (class "Default")
      (node (ref "C160") (pin "2") (pinfunction "2_2") (pintype "passive"))
      (node (ref "U9") (pin "19") (pinfunction "VDDA_19") (pintype "power_in"))
    )
    (net (code "36") (name "Net-(U9-VDDG)") (class "Default")
      (node (ref "C159") (pin "2") (pinfunction "2_2") (pintype "passive"))
      (node (ref "U9") (pin "18") (pinfunction "VDDG_18") (pintype "power_in"))
    )
    (net (code "37") (name "Net-(U9-VFB1)") (class "Default")
      (node (ref "R165") (pin "2") (pinfunction "2_2") (pintype "passive"))
      (node (ref "R166") (pin "1") (pinfunction "1_1") (pintype "passive"))
      (node (ref "U9") (pin "47") (pinfunction "VFB1_47") (pintype "input"))
    )
    (net (code "38") (name "Net-(U9-VFB2)") (class "Default")
      (node (ref "R171") (pin "2") (pinfunction "2_2") (pintype "passive"))
      (node (ref "R184") (pin "1") (pinfunction "1_1") (pintype "passive"))
      (node (ref "U9") (pin "14") (pinfunction "VFB2_14") (pintype "input"))
    )
    (net (code "39") (name "Net-(U9-VFB3)") (class "Default")
      (node (ref "R187") (pin "2") (pinfunction "2_2") (pintype "passive"))
      (node (ref "R188") (pin "1") (pinfunction "1_1") (pintype "passive"))
      (node (ref "U9") (pin "26") (pinfunction "VFB3_26") (pintype "input"))
    )
    (net (code "40") (name "Net-(U9-VFB4)") (class "Default")
      (node (ref "R191") (pin "2") (pinfunction "2_2") (pintype "passive"))
      (node (ref "R192") (pin "1") (pinfunction "1_1") (pintype "passive"))
      (node (ref "U9") (pin "35") (pinfunction "VFB4_35") (pintype "input"))
    )
    (net (code "41") (name "SYS_VDD3_3P3V") (class "Default")
      (node (ref "R40") (pin "1") (pinfunction "1_1") (pintype "passive"))
    )
    (net (code "42") (name "V3P3") (class "Default")
      (node (ref "C140") (pin "2") (pinfunction "2_2") (pintype "passive"))
      (node (ref "L11") (pin "1") (pintype "passive"))
      (node (ref "R171") (pin "1") (pinfunction "1_1") (pintype "passive"))
    )
    (net (code "43") (name "V5P0") (class "Default")
      (node (ref "C113") (pin "2") (pinfunction "2_2") (pintype "passive"))
      (node (ref "L10") (pin "1") (pintype "passive"))
      (node (ref "R165") (pin "1") (pinfunction "1_1") (pintype "passive"))
    )
    (net (code "44") (name "VADJ1") (class "Default")
      (node (ref "C146") (pin "2") (pinfunction "2_2") (pintype "passive"))
      (node (ref "L12") (pin "1") (pintype "passive"))
      (node (ref "R187") (pin "1") (pinfunction "1_1") (pintype "passive"))
    )
    (net (code "45") (name "VADJ2") (class "Default")
      (node (ref "C152") (pin "2") (pinfunction "2_2") (pintype "passive"))
      (node (ref "L13") (pin "1") (pintype "passive"))
      (node (ref "R191") (pin "1") (pinfunction "1_1") (pintype "passive"))
    )
    (net (code "46") (name "VDDD_V3P3") (class "Default")
      (node (ref "C158") (pin "2") (pinfunction "2_2") (pintype "passive"))
      (node (ref "R193") (pin "2") (pinfunction "2_2") (pintype "passive"))
      (node (ref "R195") (pin "1") (pinfunction "1_1") (pintype "passive"))
      (node (ref "U9") (pin "20") (pinfunction "VDDD_20") (pintype "power_in"))
    )
    (net (code "47") (name "VSYS") (class "Default")
      (node (ref "C112") (pin "2") (pinfunction "2_2") (pintype "passive"))
      (node (ref "C139") (pin "2") (pinfunction "2_2") (pintype "passive"))
      (node (ref "C145") (pin "2") (pinfunction "2_2") (pintype "passive"))
      (node (ref "C151") (pin "2") (pinfunction "2_2") (pintype "passive"))
      (node (ref "C156") (pin "2") (pinfunction "2_2") (pintype "passive"))
      (node (ref "U9") (pin "22") (pinfunction "VIN_22") (pintype "power_in"))
      (node (ref "U9") (pin "30") (pinfunction "PVIN3_30") (pintype "power_in"))
      (node (ref "U9") (pin "31") (pinfunction "PVIN4_31") (pintype "power_in"))
      (node (ref "U9") (pin "5") (pinfunction "PVIN1_5") (pintype "power_in"))
      (node (ref "U9") (pin "6") (pinfunction "PVIN2_6") (pintype "power_in"))
    )
    (net (code "48") (name "unconnected-(U9-CLK_OUT-Pad44)") (class "Default")
      (node (ref "U9") (pin "44") (pinfunction "CLK_OUT_44") (pintype "output+no_connect"))
    )
  )
)
